# accelero.net
KiCad netlist of a schematic drawn in Altium Designer
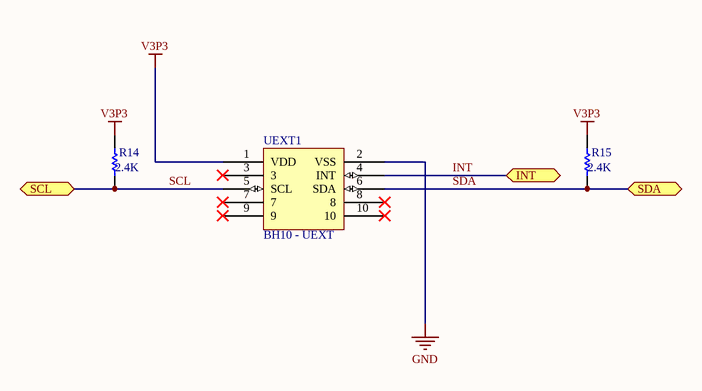
[diagram p0: accelero.SchDoc]

(export (version "E")
  (design (tool "Eeschema 10.0.6"))
  (components
    (comp (ref "R14")
      (value "2.4K")
      (footprint "RESISTANCE")
      (description "Resistor")
      (fields (field (name "Comment") "Res1") (field (name "PUBLISHER") "Altium Limited"))
      (libsource (lib "Miscellaneous Devices") (part "Res1"))
    )
    (comp (ref "R15")
      (value "2.4K")
      (footprint "RESISTANCE")
      (description "Resistor")
      (fields (field (name "Comment") "Res1") (field (name "PUBLISHER") "Altium Limited"))
      (libsource (lib "Miscellaneous Devices") (part "Res1"))
    )
    (comp (ref "UEXT1")
      (value "BH10 - UEXT")
      (footprint "ACCELERO")
      (description "Connection accelero module")
      (libsource (lib "libProject") (part "BH10 - UEXT"))
    )
  )
  (nets
    (net (code "1") (name "/INT") (class "Default")
      (node (ref "UEXT1") (pin "4") (pinfunction "INT_4") (pintype "bidirectional"))
    )
    (net (code "2") (name "/SCL") (class "Default")
      (node (ref "R14") (pin "1") (pinfunction "1_1") (pintype "passive"))
      (node (ref "UEXT1") (pin "5") (pinfunction "SCL_5") (pintype "bidirectional"))
    )
    (net (code "3") (name "/SDA") (class "Default")
      (node (ref "R15") (pin "1") (pinfunction "1_1") (pintype "passive"))
      (node (ref "UEXT1") (pin "6") (pinfunction "SDA_6") (pintype "bidirectional"))
    )
    (net (code "4") (name "GND") (class "Default")
      (node (ref "UEXT1") (pin "2") (pinfunction "VSS_2") (pintype "power_in"))
    )
    (net (code "5") (name "V3P3") (class "Default")
      (node (ref "R14") (pin "2") (pinfunction "2_2") (pintype "passive"))
      (node (ref "R15") (pin "2") (pinfunction "2_2") (pintype "passive"))
      (node (ref "UEXT1") (pin "1") (pinfunction "VDD_1") (pintype "power_in"))
    )
    (net (code "6") (name "unconnected-(UEXT1-Pad3)") (class "Default")
      (node (ref "UEXT1") (pin "3") (pinfunction "3_3") (pintype "passive+no_connect"))
    )
    (net (code "7") (name "unconnected-(UEXT1-Pad7)") (class "Default")
      (node (ref "UEXT1") (pin "7") (pinfunction "7_7") (pintype "passive+no_connect"))
    )
    (net (code "8") (name "unconnected-(UEXT1-Pad8)") (class "Default")
      (node (ref "UEXT1") (pin "8") (pinfunction "8_8") (pintype "passive+no_connect"))
    )
    (net (code "9") (name "unconnected-(UEXT1-Pad9)") (class "Default")
      (node (ref "UEXT1") (pin "9") (pinfunction "9_9") (pintype "passive+no_connect"))
    )
    (net (code "10") (name "unconnected-(UEXT1-Pad10)") (class "Default")
      (node (ref "UEXT1") (pin "10") (pinfunction "10_10") (pintype "passive+no_connect"))
    )
  )
)
